# nu_preamp.net
KiCad netlist of a schematic drawn in EAGLE
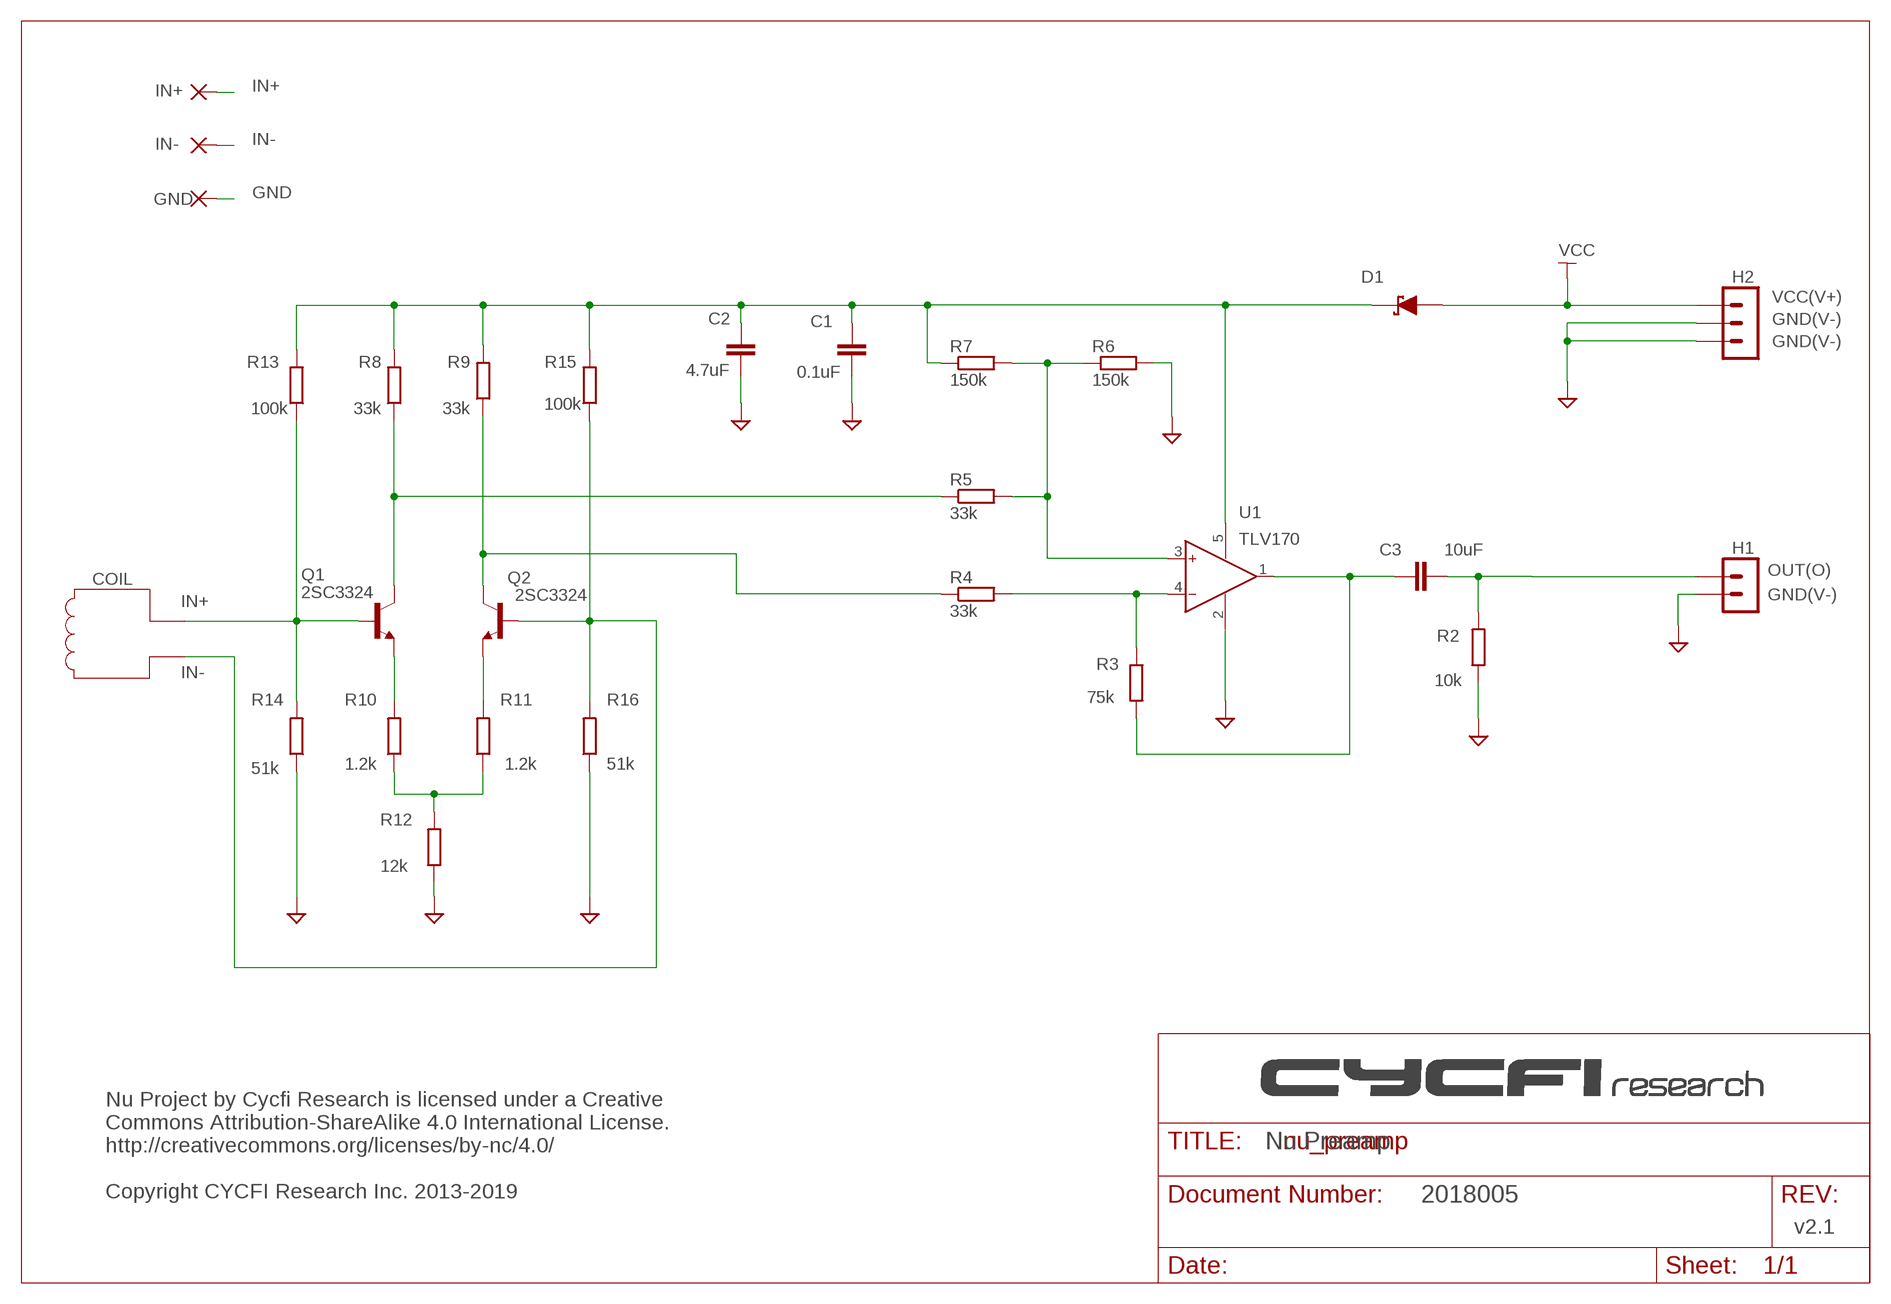
[diagram p0: schematic, sheet 1]

(export (version "E")
  (design (tool "Eeschema 10.0.6"))
  (components
    (comp (ref "C1")
      (value "0.1uF")
      (footprint "eagle-import:C0402")
      (libsource (lib "eagle-import") (part "C-EUC0402"))
    )
    (comp (ref "C2")
      (value "4.7uF")
      (footprint "eagle-import:C0603_NK")
      (libsource (lib "eagle-import") (part "C0603_NK"))
    )
    (comp (ref "C3")
      (value "10uF")
      (footprint "eagle-import:C0603_NK")
      (libsource (lib "eagle-import") (part "C0603_NK"))
    )
    (comp (ref "D1")
      (value "D_SCHOTTKYL")
      (footprint "eagle-import:SOD-323")
      (libsource (lib "eagle-import") (part "D_SCHOTTKYL"))
    )
    (comp (ref "GND")
      (value "SMD2")
      (footprint "eagle-import:SMD1,27-2,54")
      (libsource (lib "eagle-import") (part "SMD2"))
    )
    (comp (ref "H1")
      (value "2P-2MM-TH-MALE")
      (footprint "eagle-import:2P-2MM-TH")
      (libsource (lib "eagle-import") (part "2P-2MM-TH-MALE"))
    )
    (comp (ref "H2")
      (value "3P-2MM-TH-MALE")
      (footprint "eagle-import:3P-2MM-TH")
      (libsource (lib "eagle-import") (part "3P-2MM-TH-MALE"))
    )
    (comp (ref "IN+")
      (value "SMD2")
      (footprint "eagle-import:SMD1,27-2,54")
      (libsource (lib "eagle-import") (part "SMD2"))
    )
    (comp (ref "IN-")
      (value "SMD2")
      (footprint "eagle-import:SMD1,27-2,54")
      (libsource (lib "eagle-import") (part "SMD2"))
    )
    (comp (ref "Q1")
      (value "2SC3324")
      (footprint "eagle-import:SOT23")
      (libsource (lib "eagle-import") (part "2SC3324"))
    )
    (comp (ref "Q2")
      (value "2SC3324")
      (footprint "eagle-import:SOT23")
      (libsource (lib "eagle-import") (part "2SC3324"))
    )
    (comp (ref "R2")
      (value "10k")
      (footprint "eagle-import:R0402")
      (libsource (lib "eagle-import") (part "R-EU_R0402"))
    )
    (comp (ref "R3")
      (value "75k")
      (footprint "eagle-import:R0402")
      (libsource (lib "eagle-import") (part "resistor_R-EU_R0402"))
    )
    (comp (ref "R4")
      (value "33k")
      (footprint "eagle-import:R0402")
      (libsource (lib "eagle-import") (part "resistor_R-EU_R0402"))
    )
    (comp (ref "R5")
      (value "33k")
      (footprint "eagle-import:R0402")
      (libsource (lib "eagle-import") (part "resistor_R-EU_R0402"))
    )
    (comp (ref "R6")
      (value "150k")
      (footprint "eagle-import:R0402")
      (libsource (lib "eagle-import") (part "resistor_R-EU_R0402"))
    )
    (comp (ref "R7")
      (value "150k")
      (footprint "eagle-import:R0402")
      (libsource (lib "eagle-import") (part "resistor_R-EU_R0402"))
    )
    (comp (ref "R8")
      (value "33k")
      (footprint "eagle-import:R0402")
      (libsource (lib "eagle-import") (part "R-EU_R0402"))
    )
    (comp (ref "R9")
      (value "33k")
      (footprint "eagle-import:R0402")
      (libsource (lib "eagle-import") (part "R-EU_R0402"))
    )
    (comp (ref "R10")
      (value "1.2k")
      (footprint "eagle-import:R0402")
      (libsource (lib "eagle-import") (part "R-EU_R0402"))
    )
    (comp (ref "R11")
      (value "1.2k")
      (footprint "eagle-import:R0402")
      (libsource (lib "eagle-import") (part "R-EU_R0402"))
    )
    (comp (ref "R12")
      (value "12k")
      (footprint "eagle-import:R0402")
      (libsource (lib "eagle-import") (part "R-EU_R0402"))
    )
    (comp (ref "R13")
      (value "100k")
      (footprint "eagle-import:R0402")
      (libsource (lib "eagle-import") (part "R-EU_R0402"))
    )
    (comp (ref "R14")
      (value "51k")
      (footprint "eagle-import:R0402")
      (libsource (lib "eagle-import") (part "R-EU_R0402"))
    )
    (comp (ref "R15")
      (value "100k")
      (footprint "eagle-import:R0402")
      (libsource (lib "eagle-import") (part "R-EU_R0402"))
    )
    (comp (ref "R16")
      (value "51k")
      (footprint "eagle-import:R0402")
      (libsource (lib "eagle-import") (part "R-EU_R0402"))
    )
    (comp (ref "U1")
      (value "TLV170")
      (footprint "eagle-import:SOT23-5")
      (libsource (lib "eagle-import") (part "TLV170"))
    )
  )
  (nets
    (net (code "1") (name "/IN+") (class "Default")
      (node (ref "IN+") (pin "1") (pinfunction "P_1") (pintype "passive"))
      (node (ref "Q1") (pin "1") (pinfunction "B_1") (pintype "passive"))
      (node (ref "R13") (pin "1") (pinfunction "1_1") (pintype "passive"))
      (node (ref "R14") (pin "2") (pinfunction "2_2") (pintype "passive"))
    )
    (net (code "2") (name "/IN-") (class "Default")
      (node (ref "IN-") (pin "1") (pinfunction "P_1") (pintype "passive"))
      (node (ref "Q2") (pin "1") (pinfunction "B_1") (pintype "passive"))
      (node (ref "R15") (pin "1") (pinfunction "1_1") (pintype "passive"))
      (node (ref "R16") (pin "2") (pinfunction "2_2") (pintype "passive"))
    )
    (net (code "3") (name "GND") (class "Default")
      (node (ref "C1") (pin "2") (pinfunction "2_2") (pintype "passive"))
      (node (ref "C2") (pin "1") (pinfunction "1_1") (pintype "passive"))
      (node (ref "GND") (pin "1") (pinfunction "P_1") (pintype "passive"))
      (node (ref "H1") (pin "P$2") (pinfunction "2_P$2") (pintype "passive"))
      (node (ref "H2") (pin "P$2") (pinfunction "2_P$2") (pintype "passive"))
      (node (ref "H2") (pin "P$3") (pinfunction "3_P$3") (pintype "passive"))
      (node (ref "R12") (pin "1") (pinfunction "1_1") (pintype "passive"))
      (node (ref "R14") (pin "1") (pinfunction "1_1") (pintype "passive"))
      (node (ref "R16") (pin "1") (pinfunction "1_1") (pintype "passive"))
      (node (ref "R2") (pin "1") (pinfunction "1_1") (pintype "passive"))
      (node (ref "R6") (pin "2") (pinfunction "2_2") (pintype "passive"))
      (node (ref "U1") (pin "2") (pinfunction "V-_2") (pintype "power_in"))
    )
    (net (code "4") (name "Net-(D1-A)") (class "Default")
      (node (ref "D1") (pin "1") (pinfunction "A_1") (pintype "passive"))
      (node (ref "H2") (pin "P$1") (pinfunction "1_P$1") (pintype "passive"))
    )
    (net (code "5") (name "Net-(D1-C)") (class "Default")
      (node (ref "C1") (pin "1") (pinfunction "1_1") (pintype "passive"))
      (node (ref "C2") (pin "2") (pinfunction "2_2") (pintype "passive"))
      (node (ref "D1") (pin "2") (pinfunction "C_2") (pintype "passive"))
      (node (ref "R13") (pin "2") (pinfunction "2_2") (pintype "passive"))
      (node (ref "R15") (pin "2") (pinfunction "2_2") (pintype "passive"))
      (node (ref "R7") (pin "1") (pinfunction "1_1") (pintype "passive"))
      (node (ref "R8") (pin "2") (pinfunction "2_2") (pintype "passive"))
      (node (ref "R9") (pin "2") (pinfunction "2_2") (pintype "passive"))
      (node (ref "U1") (pin "5") (pinfunction "V+_5") (pintype "power_in"))
    )
    (net (code "6") (name "Net-(H1-1)") (class "Default")
      (node (ref "C3") (pin "2") (pinfunction "2_2") (pintype "passive"))
      (node (ref "H1") (pin "P$1") (pinfunction "1_P$1") (pintype "passive"))
      (node (ref "R2") (pin "2") (pinfunction "2_2") (pintype "passive"))
    )
    (net (code "7") (name "Net-(Q1-C)") (class "Default")
      (node (ref "Q1") (pin "3") (pinfunction "C_3") (pintype "passive"))
      (node (ref "R5") (pin "1") (pinfunction "1_1") (pintype "passive"))
      (node (ref "R8") (pin "1") (pinfunction "1_1") (pintype "passive"))
    )
    (net (code "8") (name "Net-(Q1-E)") (class "Default")
      (node (ref "Q1") (pin "2") (pinfunction "E_2") (pintype "passive"))
      (node (ref "R10") (pin "2") (pinfunction "2_2") (pintype "passive"))
    )
    (net (code "9") (name "Net-(Q2-C)") (class "Default")
      (node (ref "Q2") (pin "3") (pinfunction "C_3") (pintype "passive"))
      (node (ref "R4") (pin "1") (pinfunction "1_1") (pintype "passive"))
      (node (ref "R9") (pin "1") (pinfunction "1_1") (pintype "passive"))
    )
    (net (code "10") (name "Net-(Q2-E)") (class "Default")
      (node (ref "Q2") (pin "2") (pinfunction "E_2") (pintype "passive"))
      (node (ref "R11") (pin "2") (pinfunction "2_2") (pintype "passive"))
    )
    (net (code "11") (name "Net-(R10-Pad1)") (class "Default")
      (node (ref "R10") (pin "1") (pinfunction "1_1") (pintype "passive"))
      (node (ref "R11") (pin "1") (pinfunction "1_1") (pintype "passive"))
      (node (ref "R12") (pin "2") (pinfunction "2_2") (pintype "passive"))
    )
    (net (code "12") (name "Net-(U1A-IN+)") (class "Default")
      (node (ref "R5") (pin "2") (pinfunction "2_2") (pintype "passive"))
      (node (ref "R6") (pin "1") (pinfunction "1_1") (pintype "passive"))
      (node (ref "R7") (pin "2") (pinfunction "2_2") (pintype "passive"))
      (node (ref "U1") (pin "3") (pinfunction "IN+_3") (pintype "input"))
    )
    (net (code "13") (name "Net-(U1A-IN-)") (class "Default")
      (node (ref "R3") (pin "2") (pinfunction "2_2") (pintype "passive"))
      (node (ref "R4") (pin "2") (pinfunction "2_2") (pintype "passive"))
      (node (ref "U1") (pin "4") (pinfunction "IN-_4") (pintype "input"))
    )
    (net (code "14") (name "Net-(U1A-OUT)") (class "Default")
      (node (ref "C3") (pin "1") (pinfunction "1_1") (pintype "passive"))
      (node (ref "R3") (pin "1") (pinfunction "1_1") (pintype "passive"))
      (node (ref "U1") (pin "1") (pinfunction "OUT_1") (pintype "output"))
    )
  )
)
